# 4th_Order_Linwitz-Riley_Low_Pass_Filter.net
KiCad netlist of a schematic drawn in Altium Designer
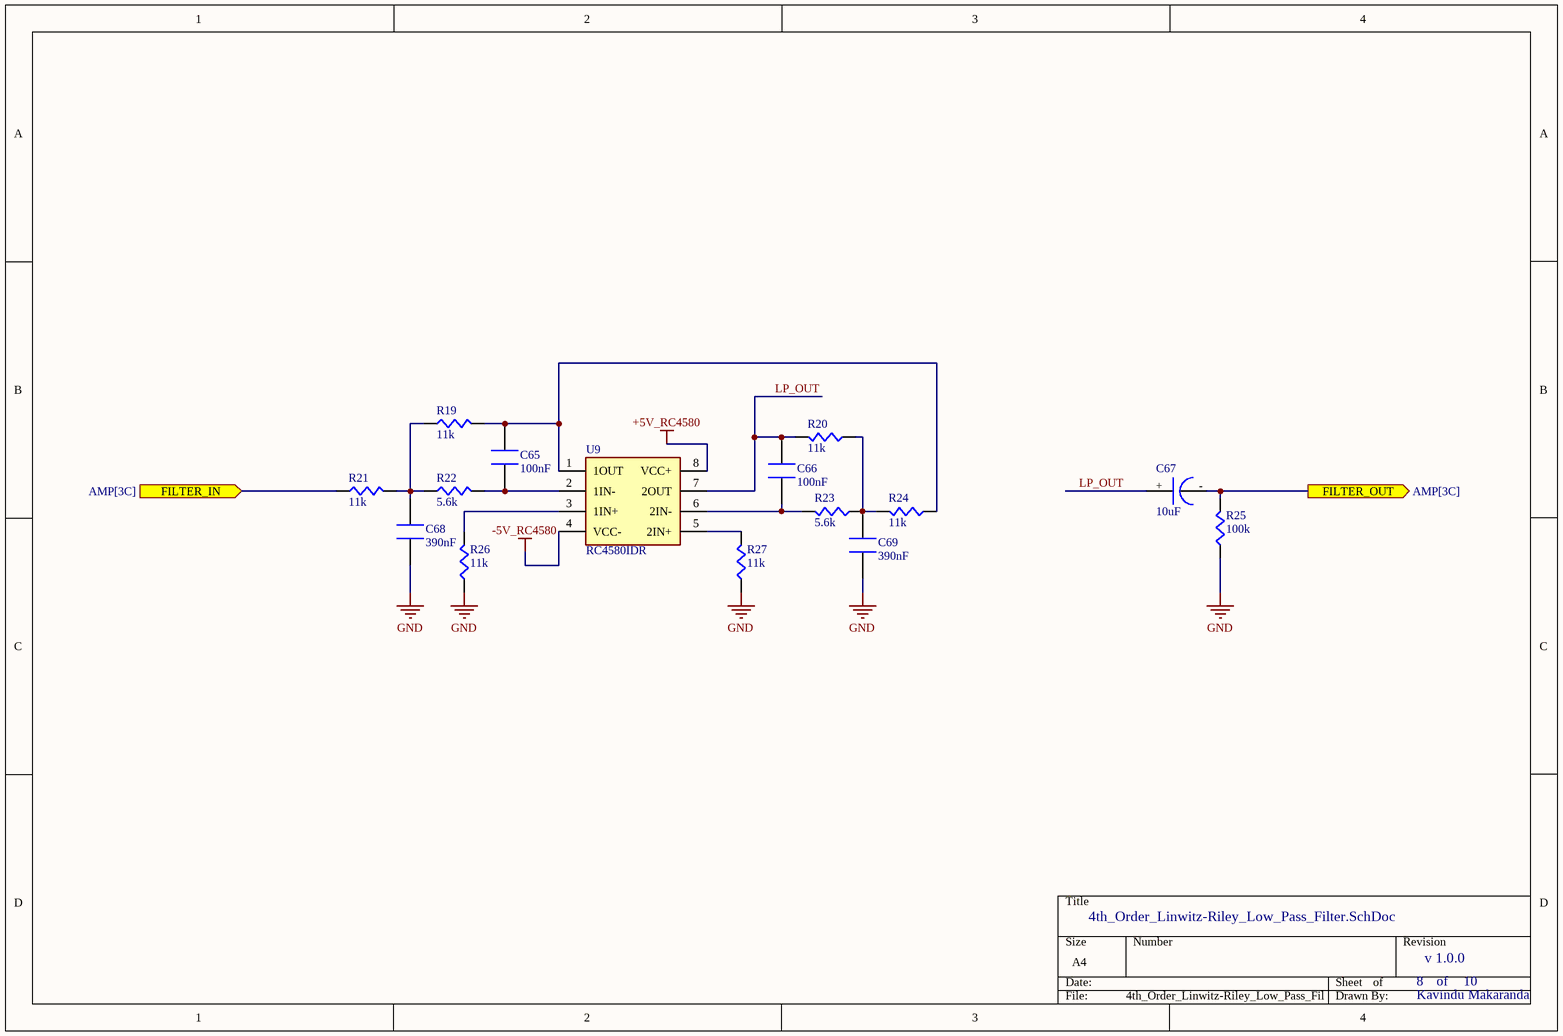
[diagram p0: 4th_Order_Linwitz-Riley_Low_Pass_Filter.SchDoc]

(export (version "E")
  (design (tool "Eeschema 10.0.6"))
  (components
    (comp (ref "C65")
      (value "100nF")
      (footprint "CAPC1206X18N")
      (libsource (lib "Schlib1") (part "CC1206_100nF_C0G"))
    )
    (comp (ref "C66")
      (value "100nF")
      (footprint "CAPC1206X18N")
      (libsource (lib "Schlib1") (part "CC1206_100nF_C0G"))
    )
    (comp (ref "C67")
      (value "10uF")
      (footprint "CAPD6.3XL5.8X61M")
      (libsource (lib "Schlib1") (part "CPD6.3XL5.8_10uF_POLYMER"))
    )
    (comp (ref "C68")
      (value "390nF")
      (footprint "CAPC0805X14N")
      (libsource (lib "Schlib1") (part "CC0805_390nF_X7R"))
    )
    (comp (ref "C69")
      (value "390nF")
      (footprint "CAPC0805X14N")
      (libsource (lib "Schlib1") (part "CC0805_390nF_X7R"))
    )
    (comp (ref "R19")
      (value "11k")
      (footprint "RECS0603X45N")
      (libsource (lib "Schlib1") (part "RESC0603_11K_THIN"))
    )
    (comp (ref "R20")
      (value "11k")
      (footprint "RECS0603X45N")
      (libsource (lib "Schlib1") (part "RESC0603_11K_THIN"))
    )
    (comp (ref "R21")
      (value "11k")
      (footprint "RECS0603X45N")
      (libsource (lib "Schlib1") (part "RESC0603_11K_THIN"))
    )
    (comp (ref "R22")
      (value "5.6k")
      (footprint "RECS0603X45N")
      (libsource (lib "Schlib1") (part "RESC0603_5.6K_THIN"))
    )
    (comp (ref "R23")
      (value "5.6k")
      (footprint "RECS0603X45N")
      (libsource (lib "Schlib1") (part "RESC0603_5.6K_THIN"))
    )
    (comp (ref "R24")
      (value "11k")
      (footprint "RECS0603X45N")
      (libsource (lib "Schlib1") (part "RESC0603_11K_THIN"))
    )
    (comp (ref "R25")
      (value "100k")
      (footprint "RECS0603X45N")
      (libsource (lib "Schlib1") (part "RESC0603_100K_THIN"))
    )
    (comp (ref "R26")
      (value "11k")
      (footprint "RECS0603X45N")
      (libsource (lib "Schlib1") (part "RESC0603_11K_THIN"))
    )
    (comp (ref "R27")
      (value "11k")
      (footprint "RECS0603X45N")
      (libsource (lib "Schlib1") (part "RESC0603_11K_THIN"))
    )
    (comp (ref "U9")
      (value "RC4580IDR")
      (footprint "SOIC127P600X175-8N")
      (fields (field (name "MOUSER PART NUMBER") "595-RC4580IDR"))
      (libsource (lib "Schlib1") (part "RC4580IDR"))
    )
  )
  (nets
    (net (code "1") (name "+5V_RC4580") (class "Default")
      (node (ref "U9") (pin "8") (pinfunction "VCC+_8") (pintype "passive"))
    )
    (net (code "2") (name "-5V_RC4580") (class "Default")
      (node (ref "U9") (pin "4") (pinfunction "VCC-_4") (pintype "passive"))
    )
    (net (code "3") (name "/FILTER_IN") (class "Default")
      (node (ref "R21") (pin "1") (pinfunction "1_1") (pintype "passive"))
    )
    (net (code "4") (name "/FILTER_OUT") (class "Default")
      (node (ref "C67") (pin "2") (pinfunction "2_2") (pintype "passive"))
      (node (ref "R25") (pin "2") (pinfunction "2_2") (pintype "passive"))
    )
    (net (code "5") (name "/LP_OUT") (class "Default")
      (node (ref "C66") (pin "1") (pinfunction "1_1") (pintype "passive"))
      (node (ref "C67") (pin "1") (pinfunction "1_1") (pintype "passive"))
      (node (ref "R20") (pin "2") (pinfunction "2_2") (pintype "passive"))
      (node (ref "U9") (pin "7") (pinfunction "2OUT_7") (pintype "passive"))
    )
    (net (code "6") (name "GND") (class "Default")
      (node (ref "C68") (pin "1") (pinfunction "1_1") (pintype "passive"))
      (node (ref "C69") (pin "2") (pinfunction "2_2") (pintype "passive"))
      (node (ref "R25") (pin "1") (pinfunction "1_1") (pintype "passive"))
      (node (ref "R26") (pin "1") (pinfunction "1_1") (pintype "passive"))
      (node (ref "R27") (pin "1") (pinfunction "1_1") (pintype "passive"))
    )
    (net (code "7") (name "Net-(C68-Pad2)") (class "Default")
      (node (ref "C68") (pin "2") (pinfunction "2_2") (pintype "passive"))
      (node (ref "R19") (pin "1") (pinfunction "1_1") (pintype "passive"))
      (node (ref "R21") (pin "2") (pinfunction "2_2") (pintype "passive"))
      (node (ref "R22") (pin "1") (pinfunction "1_1") (pintype "passive"))
    )
    (net (code "8") (name "Net-(C69-Pad1)") (class "Default")
      (node (ref "C69") (pin "1") (pinfunction "1_1") (pintype "passive"))
      (node (ref "R20") (pin "1") (pinfunction "1_1") (pintype "passive"))
      (node (ref "R23") (pin "1") (pinfunction "1_1") (pintype "passive"))
      (node (ref "R24") (pin "2") (pinfunction "2_2") (pintype "passive"))
    )
    (net (code "9") (name "Net-(U9-1IN+)") (class "Default")
      (node (ref "R26") (pin "2") (pinfunction "2_2") (pintype "passive"))
      (node (ref "U9") (pin "3") (pinfunction "1IN+_3") (pintype "passive"))
    )
    (net (code "10") (name "Net-(U9-1IN-)") (class "Default")
      (node (ref "C65") (pin "1") (pinfunction "1_1") (pintype "passive"))
      (node (ref "R22") (pin "2") (pinfunction "2_2") (pintype "passive"))
      (node (ref "U9") (pin "2") (pinfunction "1IN-_2") (pintype "passive"))
    )
    (net (code "11") (name "Net-(U9-1OUT)") (class "Default")
      (node (ref "C65") (pin "2") (pinfunction "2_2") (pintype "passive"))
      (node (ref "R19") (pin "2") (pinfunction "2_2") (pintype "passive"))
      (node (ref "R24") (pin "1") (pinfunction "1_1") (pintype "passive"))
      (node (ref "U9") (pin "1") (pinfunction "1OUT_1") (pintype "passive"))
    )
    (net (code "12") (name "Net-(U9-2IN+)") (class "Default")
      (node (ref "R27") (pin "2") (pinfunction "2_2") (pintype "passive"))
      (node (ref "U9") (pin "5") (pinfunction "2IN+_5") (pintype "passive"))
    )
    (net (code "13") (name "Net-(U9-2IN-)") (class "Default")
      (node (ref "C66") (pin "2") (pinfunction "2_2") (pintype "passive"))
      (node (ref "R23") (pin "2") (pinfunction "2_2") (pintype "passive"))
      (node (ref "U9") (pin "6") (pinfunction "2IN-_6") (pintype "passive"))
    )
  )
)
